# control.net
KiCad netlist of a schematic drawn in Altium Designer
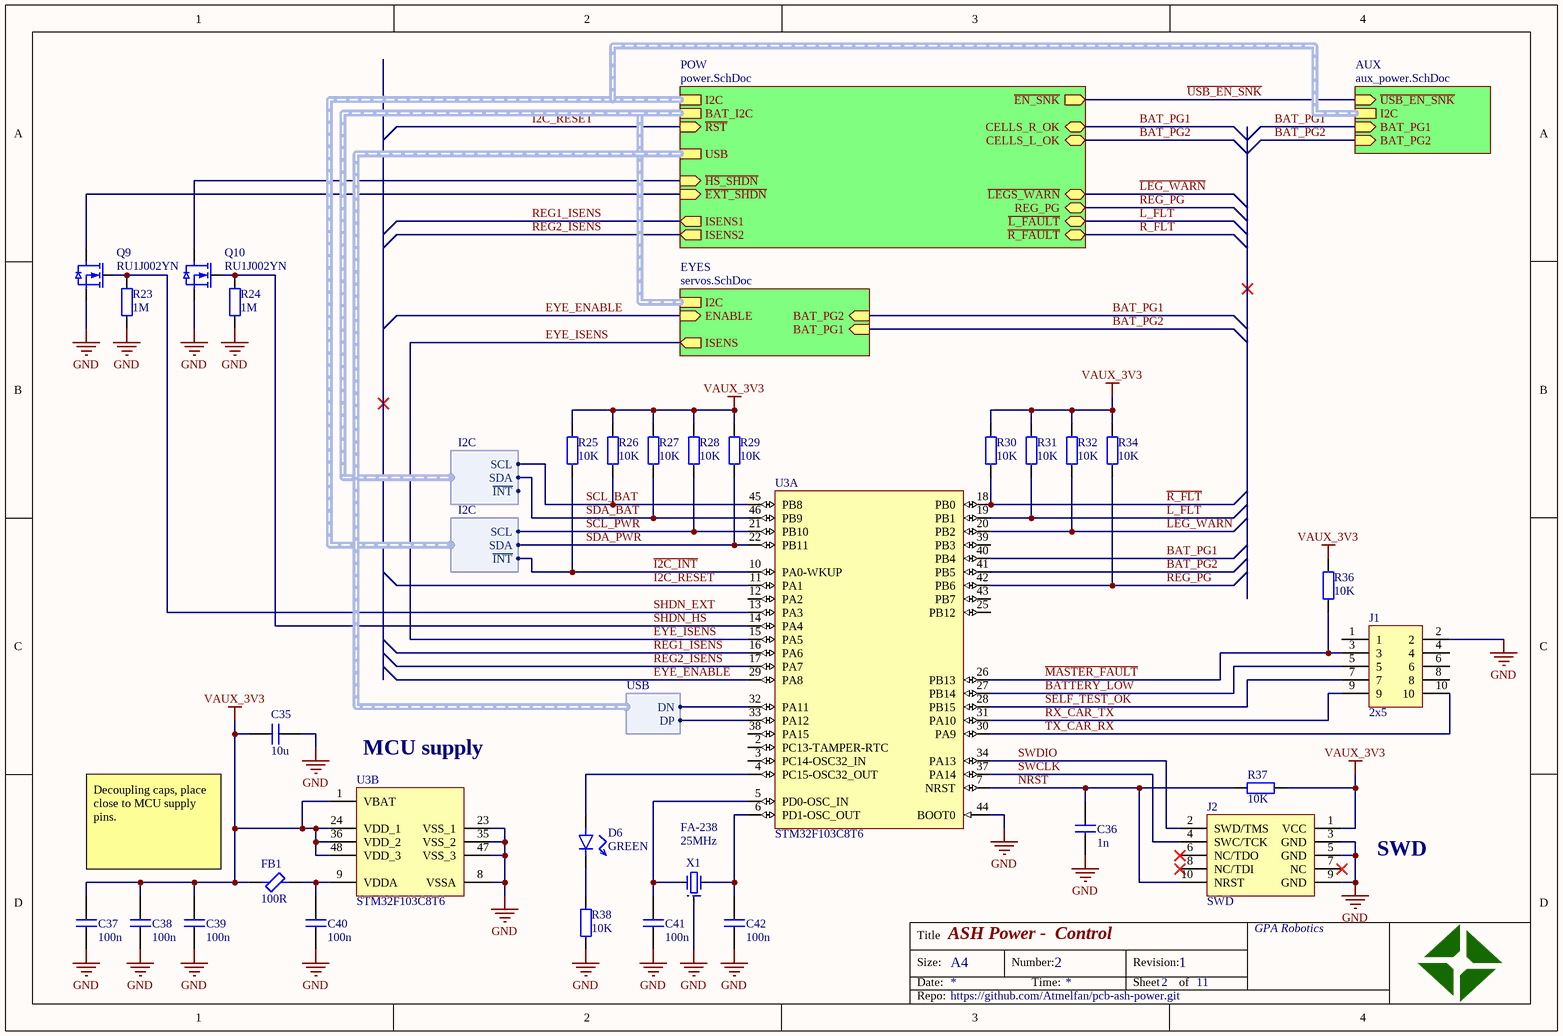
[diagram p0: control.SchDoc]

(export (version "E")
  (design (tool "Eeschema 10.0.6"))
  (components
    (comp (ref "C35")
      (value "10u")
      (footprint "CAPC3216X14N")
      (description "Capacitor")
      (fields (field (name "Comment") "cap"))
      (libsource (lib "lib_passives") (part "cap"))
    )
    (comp (ref "C36")
      (value "1n")
      (footprint "CAPC1005X06N")
      (description "Capacitor")
      (fields (field (name "Comment") "cap"))
      (libsource (lib "lib_passives") (part "cap"))
    )
    (comp (ref "C37")
      (value "100n")
      (footprint "CAPC1005X06N")
      (description "Capacitor")
      (fields (field (name "Comment") "cap"))
      (libsource (lib "lib_passives") (part "cap"))
    )
    (comp (ref "C38")
      (value "100n")
      (footprint "CAPC1005X06N")
      (description "Capacitor")
      (fields (field (name "Comment") "cap"))
      (libsource (lib "lib_passives") (part "cap"))
    )
    (comp (ref "C39")
      (value "100n")
      (footprint "CAPC1005X06N")
      (description "Capacitor")
      (fields (field (name "Comment") "cap"))
      (libsource (lib "lib_passives") (part "cap"))
    )
    (comp (ref "C40")
      (value "100n")
      (footprint "CAPC1005X06N")
      (description "Capacitor")
      (fields (field (name "Comment") "cap"))
      (libsource (lib "lib_passives") (part "cap"))
    )
    (comp (ref "C41")
      (value "100n")
      (footprint "CAPC1005X06N")
      (description "Capacitor")
      (fields (field (name "Comment") "cap"))
      (libsource (lib "lib_passives") (part "cap"))
    )
    (comp (ref "C42")
      (value "100n")
      (footprint "CAPC1005X06N")
      (description "Capacitor")
      (fields (field (name "Comment") "cap"))
      (libsource (lib "lib_passives") (part "cap"))
    )
    (comp (ref "D6")
      (value "GREEN")
      (footprint "CAPCP1005X06N")
      (description "LED")
      (fields (field (name "Comment") "led"))
      (libsource (lib "lib_actives") (part "led"))
    )
    (comp (ref "FB1")
      (value "100R")
      (footprint "INDC1005X06N")
      (description "Inductor")
      (fields (field (name "Comment") "ferrite"))
      (libsource (lib "lib_passives") (part "ferrite"))
    )
    (comp (ref "J1")
      (value "2x5")
      (footprint "hdr_2x5_50mil")
      (description "2x5 Header")
      (libsource (lib "lib_connectors") (part "hdr_2x5"))
    )
    (comp (ref "J2")
      (value "SWD")
      (footprint "hdr_2x5_50mil")
      (description "SWD Header")
      (libsource (lib "lib_connectors") (part "hdr_swd"))
    )
    (comp (ref "Q9")
      (value "RU1J002YN")
      (footprint "SOTFL65P210X105-3N")
      (description "N-channel 50V 200mA Small signal MOSFET")
      (libsource (lib "lib_rohm") (part "ru1j002yn"))
    )
    (comp (ref "Q10")
      (value "RU1J002YN")
      (footprint "SOTFL65P210X105-3N")
      (description "N-channel 50V 200mA Small signal MOSFET")
      (libsource (lib "lib_rohm") (part "ru1j002yn"))
    )
    (comp (ref "R23")
      (value "1M")
      (footprint "RESC1005X04N")
      (description "Resistor")
      (fields (field (name "Comment") "res"))
      (libsource (lib "lib_passives") (part "res"))
    )
    (comp (ref "R24")
      (value "1M")
      (footprint "RESC1005X04N")
      (description "Resistor")
      (fields (field (name "Comment") "res"))
      (libsource (lib "lib_passives") (part "res"))
    )
    (comp (ref "R25")
      (value "10K")
      (footprint "RESC1005X04N")
      (description "Resistor")
      (fields (field (name "Comment") "res"))
      (libsource (lib "lib_passives") (part "res"))
    )
    (comp (ref "R26")
      (value "10K")
      (footprint "RESC1005X04N")
      (description "Resistor")
      (fields (field (name "Comment") "res"))
      (libsource (lib "lib_passives") (part "res"))
    )
    (comp (ref "R27")
      (value "10K")
      (footprint "RESC1005X04N")
      (description "Resistor")
      (fields (field (name "Comment") "res"))
      (libsource (lib "lib_passives") (part "res"))
    )
    (comp (ref "R28")
      (value "10K")
      (footprint "RESC1005X04N")
      (description "Resistor")
      (fields (field (name "Comment") "res"))
      (libsource (lib "lib_passives") (part "res"))
    )
    (comp (ref "R29")
      (value "10K")
      (footprint "RESC1005X04N")
      (description "Resistor")
      (fields (field (name "Comment") "res"))
      (libsource (lib "lib_passives") (part "res"))
    )
    (comp (ref "R30")
      (value "10K")
      (footprint "RESC1005X04N")
      (description "Resistor")
      (fields (field (name "Comment") "res"))
      (libsource (lib "lib_passives") (part "res"))
    )
    (comp (ref "R31")
      (value "10K")
      (footprint "RESC1005X04N")
      (description "Resistor")
      (fields (field (name "Comment") "res"))
      (libsource (lib "lib_passives") (part "res"))
    )
    (comp (ref "R32")
      (value "10K")
      (footprint "RESC1005X04N")
      (description "Resistor")
      (fields (field (name "Comment") "res"))
      (libsource (lib "lib_passives") (part "res"))
    )
    (comp (ref "R34")
      (value "10K")
      (footprint "RESC1005X04N")
      (description "Resistor")
      (fields (field (name "Comment") "res"))
      (libsource (lib "lib_passives") (part "res"))
    )
    (comp (ref "R36")
      (value "10K")
      (footprint "RESC1005X04N")
      (description "Resistor")
      (fields (field (name "Comment") "res"))
      (libsource (lib "lib_passives") (part "res"))
    )
    (comp (ref "R37")
      (value "10K")
      (footprint "RESC1005X04N")
      (description "Resistor")
      (fields (field (name "Comment") "res"))
      (libsource (lib "") (part "res_1"))
    )
    (comp (ref "R38")
      (value "10K")
      (footprint "RESC1005X04N")
      (description "Resistor")
      (fields (field (name "Comment") "res"))
      (libsource (lib "lib_passives") (part "res"))
    )
    (comp (ref "U3")
      (value "STM32F103C8T6")
      (footprint "STM-LQFP48_N")
      (libsource (lib "") (part "STM32F103C8T6_1"))
    )
    (comp (ref "X1")
      (value "FA-238")
      (footprint "DFN220P320X70-4N")
      (description "Crystal With Shield")
      (fields (field (name "FREQ") "25MHz"))
      (libsource (lib "lib_passives") (part "crystal"))
    )
  )
  (nets
    (net (code "3") (name "/BATTERY_LOW") (class "Default")
      (node (ref "J1") (pin "5") (pinfunction "5_5") (pintype "passive"))
      (node (ref "U3") (pin "27") (pinfunction "PB14_27") (pintype "bidirectional"))
    )
    (net (code "4") (name "/BAT_PG1") (class "Default")
      (node (ref "U3") (pin "40") (pinfunction "PB4_40") (pintype "bidirectional"))
    )
    (net (code "5") (name "/BAT_PG2") (class "Default")
      (node (ref "U3") (pin "41") (pinfunction "PB5_41") (pintype "bidirectional"))
    )
    (net (code "6") (name "/DN") (class "Default")
      (node (ref "U3") (pin "32") (pinfunction "PA11_32") (pintype "bidirectional"))
    )
    (net (code "7") (name "/DP") (class "Default")
      (node (ref "U3") (pin "33") (pinfunction "PA12_33") (pintype "bidirectional"))
    )
    (net (code "8") (name "/EXT_SHDN") (class "Default")
      (node (ref "Q9") (pin "3") (pinfunction "D_3") (pintype "passive"))
    )
    (net (code "9") (name "/EYE_ENABLE") (class "Default")
      (node (ref "U3") (pin "29") (pinfunction "PA8_29") (pintype "bidirectional"))
    )
    (net (code "10") (name "/EYE_ISENS") (class "Default")
      (node (ref "U3") (pin "15") (pinfunction "PA5_15") (pintype "bidirectional"))
    )
    (net (code "11") (name "/HS_SHDN") (class "Default")
      (node (ref "Q10") (pin "3") (pinfunction "D_3") (pintype "passive"))
    )
    (net (code "12") (name "/I2C_INT") (class "Default")
      (node (ref "R25") (pin "1") (pinfunction "1_1") (pintype "passive"))
      (node (ref "U3") (pin "10") (pinfunction "PA0-WKUP_10") (pintype "bidirectional"))
    )
    (net (code "13") (name "/I2C_RESET") (class "Default")
      (node (ref "U3") (pin "11") (pinfunction "PA1_11") (pintype "bidirectional"))
    )
    (net (code "14") (name "/LEG_WARN") (class "Default")
      (node (ref "R32") (pin "1") (pinfunction "1_1") (pintype "passive"))
      (node (ref "U3") (pin "20") (pinfunction "PB2_20") (pintype "bidirectional"))
    )
    (net (code "15") (name "/L_FLT") (class "Default")
      (node (ref "R31") (pin "1") (pinfunction "1_1") (pintype "passive"))
      (node (ref "U3") (pin "19") (pinfunction "PB1_19") (pintype "bidirectional"))
    )
    (net (code "16") (name "/MASTER_FAULT") (class "Default")
      (node (ref "J1") (pin "3") (pinfunction "3_3") (pintype "passive"))
      (node (ref "R36") (pin "1") (pinfunction "1_1") (pintype "passive"))
      (node (ref "U3") (pin "26") (pinfunction "PB13_26") (pintype "bidirectional"))
    )
    (net (code "17") (name "/NRST") (class "Default")
      (node (ref "C36") (pin "2") (pinfunction "2_2") (pintype "passive"))
      (node (ref "J2") (pin "10") (pinfunction "NRST_10") (pintype "passive"))
      (node (ref "R37") (pin "2") (pinfunction "2_2") (pintype "passive"))
      (node (ref "U3") (pin "7") (pinfunction "NRST_7") (pintype "bidirectional"))
    )
    (net (code "18") (name "/REG1_ISENS") (class "Default")
      (node (ref "U3") (pin "16") (pinfunction "PA6_16") (pintype "bidirectional"))
    )
    (net (code "19") (name "/REG2_ISENS") (class "Default")
      (node (ref "U3") (pin "17") (pinfunction "PA7_17") (pintype "bidirectional"))
    )
    (net (code "20") (name "/REG_PG") (class "Default")
      (node (ref "R34") (pin "1") (pinfunction "1_1") (pintype "passive"))
      (node (ref "U3") (pin "42") (pinfunction "PB6_42") (pintype "bidirectional"))
    )
    (net (code "21") (name "/RX_CAR_TX") (class "Default")
      (node (ref "J1") (pin "9") (pinfunction "9_9") (pintype "passive"))
      (node (ref "U3") (pin "31") (pinfunction "PA10_31") (pintype "bidirectional"))
    )
    (net (code "22") (name "/R_FLT") (class "Default")
      (node (ref "R30") (pin "1") (pinfunction "1_1") (pintype "passive"))
      (node (ref "U3") (pin "18") (pinfunction "PB0_18") (pintype "bidirectional"))
    )
    (net (code "23") (name "/SCL_BAT") (class "Default")
      (node (ref "R26") (pin "1") (pinfunction "1_1") (pintype "passive"))
      (node (ref "U3") (pin "45") (pinfunction "PB8_45") (pintype "bidirectional"))
    )
    (net (code "24") (name "/SCL_PWR") (class "Default")
      (node (ref "R28") (pin "1") (pinfunction "1_1") (pintype "passive"))
      (node (ref "U3") (pin "21") (pinfunction "PB10_21") (pintype "bidirectional"))
    )
    (net (code "25") (name "/SDA_BAT") (class "Default")
      (node (ref "R27") (pin "1") (pinfunction "1_1") (pintype "passive"))
      (node (ref "U3") (pin "46") (pinfunction "PB9_46") (pintype "bidirectional"))
    )
    (net (code "26") (name "/SDA_PWR") (class "Default")
      (node (ref "R29") (pin "1") (pinfunction "1_1") (pintype "passive"))
      (node (ref "U3") (pin "22") (pinfunction "PB11_22") (pintype "bidirectional"))
    )
    (net (code "27") (name "/SELF_TEST_OK") (class "Default")
      (node (ref "J1") (pin "7") (pinfunction "7_7") (pintype "passive"))
      (node (ref "U3") (pin "28") (pinfunction "PB15_28") (pintype "bidirectional"))
    )
    (net (code "28") (name "/SHDN_EXT") (class "Default")
      (node (ref "Q9") (pin "1") (pinfunction "G_1") (pintype "passive"))
      (node (ref "R23") (pin "2") (pinfunction "2_2") (pintype "passive"))
      (node (ref "U3") (pin "13") (pinfunction "PA3_13") (pintype "bidirectional"))
    )
    (net (code "29") (name "/SHDN_HS") (class "Default")
      (node (ref "Q10") (pin "1") (pinfunction "G_1") (pintype "passive"))
      (node (ref "R24") (pin "2") (pinfunction "2_2") (pintype "passive"))
      (node (ref "U3") (pin "14") (pinfunction "PA4_14") (pintype "bidirectional"))
    )
    (net (code "30") (name "/SWCLK") (class "Default")
      (node (ref "J2") (pin "4") (pinfunction "SWC/TCK_4") (pintype "passive"))
      (node (ref "U3") (pin "37") (pinfunction "PA14_37") (pintype "bidirectional"))
    )
    (net (code "31") (name "/SWDIO") (class "Default")
      (node (ref "J2") (pin "2") (pinfunction "SWD/TMS_2") (pintype "passive"))
      (node (ref "U3") (pin "34") (pinfunction "PA13_34") (pintype "bidirectional"))
    )
    (net (code "32") (name "/TX_CAR_RX") (class "Default")
      (node (ref "J1") (pin "10") (pinfunction "10_10") (pintype "passive"))
      (node (ref "U3") (pin "30") (pinfunction "PA9_30") (pintype "bidirectional"))
    )
    (net (code "36") (name "GND") (class "Default")
      (node (ref "C35") (pin "2") (pinfunction "2_2") (pintype "passive"))
      (node (ref "C36") (pin "1") (pinfunction "1_1") (pintype "passive"))
      (node (ref "C37") (pin "1") (pinfunction "1_1") (pintype "passive"))
      (node (ref "C38") (pin "1") (pinfunction "1_1") (pintype "passive"))
      (node (ref "C39") (pin "1") (pinfunction "1_1") (pintype "passive"))
      (node (ref "C40") (pin "1") (pinfunction "1_1") (pintype "passive"))
      (node (ref "C41") (pin "1") (pinfunction "1_1") (pintype "passive"))
      (node (ref "C42") (pin "1") (pinfunction "1_1") (pintype "passive"))
      (node (ref "J1") (pin "2") (pinfunction "2_2") (pintype "passive"))
      (node (ref "J2") (pin "3") (pinfunction "GND_3") (pintype "passive"))
      (node (ref "J2") (pin "5") (pinfunction "GND_5") (pintype "passive"))
      (node (ref "J2") (pin "9") (pinfunction "GND_9") (pintype "passive"))
      (node (ref "Q10") (pin "2") (pinfunction "S_2") (pintype "passive"))
      (node (ref "Q9") (pin "2") (pinfunction "S_2") (pintype "passive"))
      (node (ref "R23") (pin "1") (pinfunction "1_1") (pintype "passive"))
      (node (ref "R24") (pin "1") (pinfunction "1_1") (pintype "passive"))
      (node (ref "R38") (pin "1") (pinfunction "1_1") (pintype "passive"))
      (node (ref "U3") (pin "23") (pinfunction "VSS_1_23") (pintype "power_in"))
      (node (ref "U3") (pin "35") (pinfunction "VSS_2_35") (pintype "power_in"))
      (node (ref "U3") (pin "44") (pinfunction "BOOT0_44") (pintype "input"))
      (node (ref "U3") (pin "47") (pinfunction "VSS_3_47") (pintype "power_in"))
      (node (ref "U3") (pin "8") (pinfunction "VSSA_8") (pintype "power_in"))
      (node (ref "X1") (pin "SHIELD") (pinfunction "SHIELD_SHIELD") (pintype "passive"))
    )
    (net (code "37") (name "Net-(D6-PadC)") (class "Default")
      (node (ref "D6") (pin "C") (pinfunction "C_C") (pintype "passive"))
      (node (ref "R38") (pin "2") (pinfunction "2_2") (pintype "passive"))
    )
    (net (code "38") (name "Net-(U3A-PC15-OSC32_OUT)") (class "Default")
      (node (ref "D6") (pin "A") (pinfunction "A_A") (pintype "passive"))
      (node (ref "U3") (pin "4") (pinfunction "PC15-OSC32_OUT_4") (pintype "bidirectional"))
    )
    (net (code "39") (name "Net-(U3A-PD0-OSC_IN)") (class "Default")
      (node (ref "C41") (pin "2") (pinfunction "2_2") (pintype "passive"))
      (node (ref "U3") (pin "5") (pinfunction "PD0-OSC_IN_5") (pintype "bidirectional"))
      (node (ref "X1") (pin "1") (pinfunction "1_1") (pintype "passive"))
    )
    (net (code "40") (name "Net-(U3A-PD1-OSC_OUT)") (class "Default")
      (node (ref "C42") (pin "2") (pinfunction "2_2") (pintype "passive"))
      (node (ref "U3") (pin "6") (pinfunction "PD1-OSC_OUT_6") (pintype "bidirectional"))
      (node (ref "X1") (pin "2") (pinfunction "2_2") (pintype "passive"))
    )
    (net (code "41") (name "Net-(U3B-VDDA)") (class "Default")
      (node (ref "C40") (pin "2") (pinfunction "2_2") (pintype "passive"))
      (node (ref "FB1") (pin "2") (pinfunction "2_2") (pintype "passive"))
      (node (ref "U3") (pin "9") (pinfunction "VDDA_9") (pintype "power_in"))
    )
    (net (code "42") (name "VAUX_3V3") (class "Default")
      (node (ref "C35") (pin "1") (pinfunction "1_1") (pintype "passive"))
      (node (ref "C37") (pin "2") (pinfunction "2_2") (pintype "passive"))
      (node (ref "C38") (pin "2") (pinfunction "2_2") (pintype "passive"))
      (node (ref "C39") (pin "2") (pinfunction "2_2") (pintype "passive"))
      (node (ref "FB1") (pin "1") (pinfunction "1_1") (pintype "passive"))
      (node (ref "J2") (pin "1") (pinfunction "VCC_1") (pintype "passive"))
      (node (ref "R25") (pin "2") (pinfunction "2_2") (pintype "passive"))
      (node (ref "R26") (pin "2") (pinfunction "2_2") (pintype "passive"))
      (node (ref "R27") (pin "2") (pinfunction "2_2") (pintype "passive"))
      (node (ref "R28") (pin "2") (pinfunction "2_2") (pintype "passive"))
      (node (ref "R29") (pin "2") (pinfunction "2_2") (pintype "passive"))
      (node (ref "R30") (pin "2") (pinfunction "2_2") (pintype "passive"))
      (node (ref "R31") (pin "2") (pinfunction "2_2") (pintype "passive"))
      (node (ref "R32") (pin "2") (pinfunction "2_2") (pintype "passive"))
      (node (ref "R34") (pin "2") (pinfunction "2_2") (pintype "passive"))
      (node (ref "R36") (pin "2") (pinfunction "2_2") (pintype "passive"))
      (node (ref "R37") (pin "1") (pinfunction "1_1") (pintype "passive"))
      (node (ref "U3") (pin "1") (pinfunction "VBAT_1") (pintype "power_in"))
      (node (ref "U3") (pin "24") (pinfunction "VDD_1_24") (pintype "power_in"))
      (node (ref "U3") (pin "36") (pinfunction "VDD_2_36") (pintype "power_in"))
      (node (ref "U3") (pin "48") (pinfunction "VDD_3_48") (pintype "power_in"))
    )
    (net (code "43") (name "unconnected-(J1-Pad1)") (class "Default")
      (node (ref "J1") (pin "1") (pinfunction "1_1") (pintype "passive"))
    )
    (net (code "44") (name "unconnected-(J1-Pad4)") (class "Default")
      (node (ref "J1") (pin "4") (pinfunction "4_4") (pintype "passive"))
    )
    (net (code "45") (name "unconnected-(J1-Pad6)") (class "Default")
      (node (ref "J1") (pin "6") (pinfunction "6_6") (pintype "passive"))
    )
    (net (code "46") (name "unconnected-(J1-Pad8)") (class "Default")
      (node (ref "J1") (pin "8") (pinfunction "8_8") (pintype "passive"))
    )
    (net (code "47") (name "unconnected-(J2-NC-Pad7)") (class "Default")
      (node (ref "J2") (pin "7") (pinfunction "NC_7") (pintype "passive+no_connect"))
    )
    (net (code "48") (name "unconnected-(J2-NC{slash}TDI-Pad8)") (class "Default")
      (node (ref "J2") (pin "8") (pinfunction "NC/TDI_8") (pintype "passive+no_connect"))
    )
    (net (code "49") (name "unconnected-(J2-NC{slash}TDO-Pad6)") (class "Default")
      (node (ref "J2") (pin "6") (pinfunction "NC/TDO_6") (pintype "passive+no_connect"))
    )
    (net (code "50") (name "unconnected-(U3A-PA2-Pad12)") (class "Default")
      (node (ref "U3") (pin "12") (pinfunction "PA2_12") (pintype "bidirectional"))
    )
    (net (code "51") (name "unconnected-(U3A-PA15-Pad38)") (class "Default")
      (node (ref "U3") (pin "38") (pinfunction "PA15_38") (pintype "bidirectional"))
    )
    (net (code "52") (name "unconnected-(U3A-PB3-Pad39)") (class "Default")
      (node (ref "U3") (pin "39") (pinfunction "PB3_39") (pintype "bidirectional"))
    )
    (net (code "53") (name "unconnected-(U3A-PB7-Pad43)") (class "Default")
      (node (ref "U3") (pin "43") (pinfunction "PB7_43") (pintype "bidirectional"))
    )
    (net (code "54") (name "unconnected-(U3A-PB12-Pad25)") (class "Default")
      (node (ref "U3") (pin "25") (pinfunction "PB12_25") (pintype "bidirectional"))
    )
    (net (code "55") (name "unconnected-(U3A-PC13-TAMPER-RTC-Pad2)") (class "Default")
      (node (ref "U3") (pin "2") (pinfunction "PC13-TAMPER-RTC_2") (pintype "bidirectional"))
    )
    (net (code "56") (name "unconnected-(U3A-PC14-OSC32_IN-Pad3)") (class "Default")
      (node (ref "U3") (pin "3") (pinfunction "PC14-OSC32_IN_3") (pintype "bidirectional"))
    )
  )
)
